# Communication.net
KiCad netlist of a schematic drawn in Altium Designer
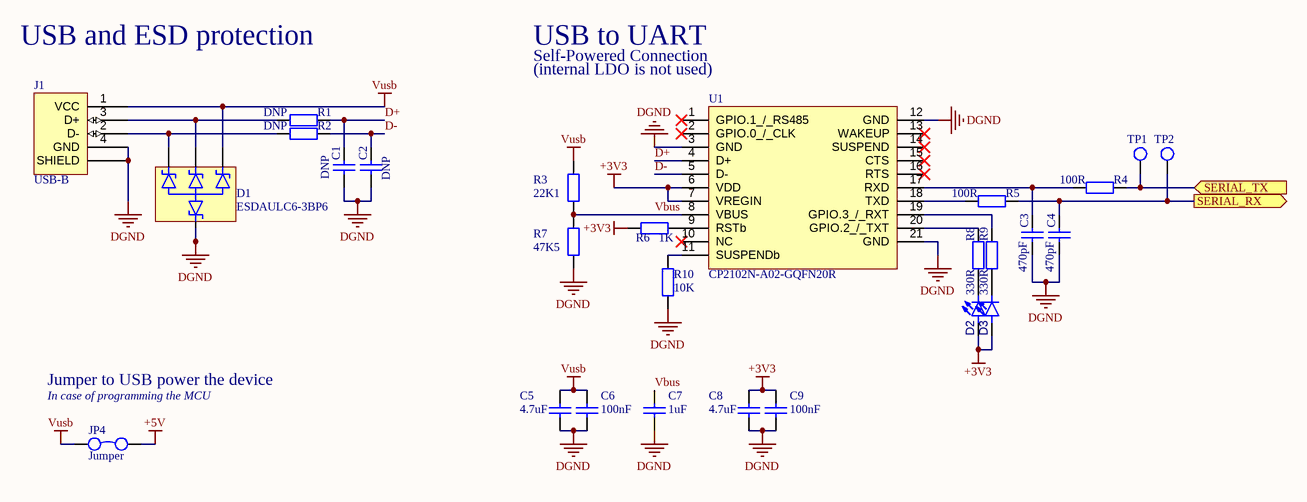
[diagram p0: Communication.SchDoc]

(export (version "E")
  (design (tool "Eeschema 10.0.6"))
  (components
    (comp (ref "C1")
      (value "DNP")
      (footprint "CAP0603")
      (fields
        (field (name "MANUFACTURER") "KEMET")
        (field (name "MANUFACTURER PART NUMBER") "C0603C470J1GACTU")
      )
      (libsource (lib "UPS_Schlib") (part "47pF"))
    )
    (comp (ref "C2")
      (value "DNP")
      (footprint "CAP0603")
      (fields
        (field (name "MANUFACTURER") "KEMET")
        (field (name "MANUFACTURER PART NUMBER") "C0603C470J1GACTU")
      )
      (libsource (lib "UPS_Schlib") (part "47pF"))
    )
    (comp (ref "C3")
      (value "470pF")
      (footprint "CAP0603")
      (fields
        (field (name "MANUFACTURER") "KEMET")
        (field (name "MANUFACTURER PART NUMBER") "C0603C471JAGACAUTO")
      )
      (libsource (lib "UPS_Schlib") (part "470pF"))
    )
    (comp (ref "C4")
      (value "470pF")
      (footprint "CAP0603")
      (fields
        (field (name "MANUFACTURER") "KEMET")
        (field (name "MANUFACTURER PART NUMBER") "C0603C471JAGACAUTO")
      )
      (libsource (lib "UPS_Schlib") (part "470pF"))
    )
    (comp (ref "C5")
      (value "4.7uF")
      (footprint "CAP0603")
      (description "Capacitor Ceramic 4.7uF 10V X5R 10% 0603 T/R")
      (fields
        (field (name "MANUFACTURER") "Samsung")
        (field (name "MANUFACTURER PART NUMBER") "CL10A475KP8NNWC")
      )
      (libsource (lib "UPS_Schlib") (part "4.7uF"))
    )
    (comp (ref "C6")
      (value "100nF")
      (footprint "CAP0603")
      (fields
        (field (name "MANUFACTURER") "Samsung")
        (field (name "MANUFACTURER PART NUMBER") "CL10B104KA8WPNC")
      )
      (libsource (lib "UPS_Schlib") (part "100nF"))
    )
    (comp (ref "C7")
      (value "1uF")
      (footprint "CAP0603")
      (fields
        (field (name "MANUFACTURER") "Walsin Technologies")
        (field (name "MANUFACTURER PART NUMBER") "SH18B105K160CT")
      )
      (libsource (lib "UPS_Schlib") (part "1uF"))
    )
    (comp (ref "C8")
      (value "4.7uF")
      (footprint "CAP0603")
      (description "Capacitor Ceramic 4.7uF 10V X5R 10% 0603 T/R")
      (fields
        (field (name "MANUFACTURER") "Samsung")
        (field (name "MANUFACTURER PART NUMBER") "CL10A475KP8NNWC")
      )
      (libsource (lib "UPS_Schlib") (part "4.7uF"))
    )
    (comp (ref "C9")
      (value "100nF")
      (footprint "CAP0603")
      (fields
        (field (name "MANUFACTURER") "Samsung")
        (field (name "MANUFACTURER PART NUMBER") "CL10B104KA8WPNC")
      )
      (libsource (lib "UPS_Schlib") (part "100nF"))
    )
    (comp (ref "D1")
      (value "ESDAULC6-3BP6")
      (footprint "SOT-666")
      (description "Trans Voltage Suppressor Diode, Bidirectional, 4 Element, Silicon")
      (fields
        (field (name "MOUSER PART NUMBER") "511-ESDAULC63BP6")
        (field (name "MANUFACTURER") "STMicroelectronics")
      )
      (libsource (lib "UPS_Schlib") (part "ESDAULC6-3BP6"))
    )
    (comp (ref "D2")
      (value "~")
      (footprint "LED0603")
      (description "Single Color LED, Bright Green, Water Clear, 1.1mm")
      (fields
        (field (name "MANUFACTURER") "Wurth Electronics")
        (field (name "MANUFACTURER PART NUMBER") "150060VS75000")
      )
      (libsource (lib "UPS_Schlib") (part "LED Green"))
    )
    (comp (ref "D3")
      (value "~")
      (footprint "LED0603")
      (description "Single Color LED, Bright Green, Water Clear, 1.1mm")
      (fields
        (field (name "MANUFACTURER") "Wurth Electronics")
        (field (name "MANUFACTURER PART NUMBER") "150060VS75000")
      )
      (libsource (lib "UPS_Schlib") (part "LED Green"))
    )
    (comp (ref "J1")
      (value "USB-B")
      (footprint "USB-B-FEMALE")
      (description "USB Connector, 4 Contact(s), Female, Right Angle, Solder Terminal, Receptacle")
      (fields
        (field (name "MANUFACTURER") "CUI Devices")
        (field (name "MANUFACTURER PART NUMBER") "UJ2-BH-W2-TH")
      )
      (libsource (lib "UPS_Schlib") (part "USB-B"))
    )
    (comp (ref "JP4")
      (value "Jumper")
      (footprint "PIN-1X2")
      (description "Interconnection Device")
      (fields (field (name "MANUFACTURER") "Harwin") (field (name "MANUFACTURER PART NUMBER") "M7582-46"))
      (libsource (lib "UPS_Schlib") (part "Jumper"))
    )
    (comp (ref "R1")
      (value "DNP")
      (footprint "RES0603")
      (fields
        (field (name "MANUFACTURER") "Vishay")
        (field (name "MANUFACTURER PART NUMBER") "CRCW060320R0FKEA")
      )
      (libsource (lib "UPS_Schlib") (part "20R"))
    )
    (comp (ref "R2")
      (value "DNP")
      (footprint "RES0603")
      (fields
        (field (name "MANUFACTURER") "Vishay")
        (field (name "MANUFACTURER PART NUMBER") "CRCW060320R0FKEA")
      )
      (libsource (lib "UPS_Schlib") (part "20R"))
    )
    (comp (ref "R3")
      (value "22K1")
      (footprint "RES0603")
      (description "22.1K F 1/16 0603")
      (fields
        (field (name "MANUFACTURER") "Mitsubishi Kamaya")
        (field (name "MANUFACTURER PART NUMBER") "RMC1/16K2212FTP")
      )
      (libsource (lib "UPS_Schlib") (part "22K1"))
    )
    (comp (ref "R4")
      (value "100R")
      (footprint "RES0603")
      (fields
        (field (name "MANUFACTURER") "Yageo")
        (field (name "MANUFACTURER PART NUMBER") "RC0603JR-13100RL")
      )
      (libsource (lib "UPS_Schlib") (part "100R"))
    )
    (comp (ref "R5")
      (value "100R")
      (footprint "RES0603")
      (fields
        (field (name "MANUFACTURER") "Yageo")
        (field (name "MANUFACTURER PART NUMBER") "RC0603JR-13100RL")
      )
      (libsource (lib "UPS_Schlib") (part "100R"))
    )
    (comp (ref "R6")
      (value "1K")
      (footprint "RES0603")
      (fields
        (field (name "MANUFACTURER") "Bourns")
        (field (name "MANUFACTURER PART NUMBER") "CR0603-FX-1001ELF")
      )
      (libsource (lib "UPS_Schlib") (part "1K"))
    )
    (comp (ref "R7")
      (value "47K5")
      (footprint "RES0603")
      (fields
        (field (name "MANUFACTURER") "Yageo")
        (field (name "MANUFACTURER PART NUMBER") "RC0603FR-0747K5L")
      )
      (libsource (lib "UPS_Schlib") (part "47K5"))
    )
    (comp (ref "R8")
      (value "330R")
      (footprint "RES0603")
      (fields
        (field (name "MANUFACTURER") "Walsin Technologies")
        (field (name "MANUFACTURER PART NUMBER") "WR06X3300FTL")
      )
      (libsource (lib "UPS_Schlib") (part "330R"))
    )
    (comp (ref "R9")
      (value "330R")
      (footprint "RES0603")
      (fields
        (field (name "MANUFACTURER") "Walsin Technologies")
        (field (name "MANUFACTURER PART NUMBER") "WR06X3300FTL")
      )
      (libsource (lib "UPS_Schlib") (part "330R"))
    )
    (comp (ref "R10")
      (value "10K")
      (footprint "RES0603")
      (fields
        (field (name "MANUFACTURER") "Bourns")
        (field (name "MANUFACTURER PART NUMBER") "CR0603-FX-1002ELF")
      )
      (libsource (lib "UPS_Schlib") (part "10K"))
    )
    (comp (ref "TP1")
      (value "Test Point")
      (footprint "TP-1.5HOLE")
      (libsource (lib "UPS_Schlib") (part "Test Point"))
    )
    (comp (ref "TP2")
      (value "Test Point")
      (footprint "TP-1.5HOLE")
      (libsource (lib "UPS_Schlib") (part "Test Point"))
    )
    (comp (ref "U1")
      (value "CP2102N-A02-GQFN20R")
      (footprint "QFN-20")
      (description "USB Bus Controller, CMOS")
      (fields
        (field (name "MOUSER PART NUMBER") "634-CP2102NA02QFN20R")
        (field (name "MANUFACTURER") "Silicon Labs")
      )
      (libsource (lib "UPS_Schlib") (part "CP2102N-A02-GQFN20R"))
    )
  )
  (nets
    (net (code "1") (name "+3V3") (class "Default")
      (node (ref "C8") (pin "2") (pinfunction "2_2") (pintype "passive"))
      (node (ref "C9") (pin "1") (pinfunction "1_1") (pintype "passive"))
      (node (ref "D2") (pin "2") (pinfunction "A_2") (pintype "passive"))
      (node (ref "D3") (pin "2") (pinfunction "A_2") (pintype "passive"))
      (node (ref "R6") (pin "1") (pinfunction "1_1") (pintype "passive"))
      (node (ref "U1") (pin "6") (pinfunction "VDD_6") (pintype "passive"))
      (node (ref "U1") (pin "7") (pinfunction "VREGIN_7") (pintype "passive"))
    )
    (net (code "2") (name "+5V") (class "Default") (node (ref "JP4") (pin "2") (pintype "passive")))
    (net (code "3") (name "/D+") (class "Default")
      (node (ref "C1") (pin "2") (pinfunction "2_2") (pintype "passive"))
      (node (ref "R1") (pin "1") (pinfunction "1_1") (pintype "passive"))
      (node (ref "U1") (pin "4") (pinfunction "D+_4") (pintype "passive"))
    )
    (net (code "4") (name "/D-") (class "Default")
      (node (ref "C2") (pin "2") (pinfunction "2_2") (pintype "passive"))
      (node (ref "R2") (pin "1") (pinfunction "1_1") (pintype "passive"))
      (node (ref "U1") (pin "5") (pinfunction "D-_5") (pintype "passive"))
    )
    (net (code "5") (name "/SERIAL_RX") (class "Default")
      (node (ref "C4") (pin "2") (pinfunction "2_2") (pintype "passive"))
      (node (ref "R5") (pin "2") (pinfunction "2_2") (pintype "passive"))
      (node (ref "TP2") (pin "1") (pintype "passive"))
    )
    (net (code "6") (name "/SERIAL_TX") (class "Default")
      (node (ref "R4") (pin "2") (pinfunction "2_2") (pintype "passive"))
      (node (ref "TP1") (pin "1") (pintype "passive"))
    )
    (net (code "7") (name "/Vbus") (class "Default")
      (node (ref "C7") (pin "2") (pinfunction "2_2") (pintype "passive"))
      (node (ref "R3") (pin "1") (pinfunction "1_1") (pintype "passive"))
      (node (ref "R7") (pin "2") (pinfunction "2_2") (pintype "passive"))
      (node (ref "U1") (pin "8") (pinfunction "VBUS_8") (pintype "passive"))
    )
    (net (code "8") (name "DGND") (class "Default")
      (node (ref "C1") (pin "1") (pinfunction "1_1") (pintype "passive"))
      (node (ref "C2") (pin "1") (pinfunction "1_1") (pintype "passive"))
      (node (ref "C3") (pin "1") (pinfunction "1_1") (pintype "passive"))
      (node (ref "C4") (pin "1") (pinfunction "1_1") (pintype "passive"))
      (node (ref "C5") (pin "1") (pinfunction "1_1") (pintype "passive"))
      (node (ref "C6") (pin "2") (pinfunction "2_2") (pintype "passive"))
      (node (ref "C7") (pin "1") (pinfunction "1_1") (pintype "passive"))
      (node (ref "C8") (pin "1") (pinfunction "1_1") (pintype "passive"))
      (node (ref "C9") (pin "2") (pinfunction "2_2") (pintype "passive"))
      (node (ref "D1") (pin "6") (pinfunction "GND_6") (pintype "passive"))
      (node (ref "J1") (pin "0") (pinfunction "SHIELD_0") (pintype "passive"))
      (node (ref "J1") (pin "4") (pinfunction "GND_4") (pintype "passive"))
      (node (ref "R10") (pin "1") (pinfunction "1_1") (pintype "passive"))
      (node (ref "R7") (pin "1") (pinfunction "1_1") (pintype "passive"))
      (node (ref "U1") (pin "12") (pinfunction "GND_12") (pintype "passive"))
      (node (ref "U1") (pin "21") (pinfunction "GND_21") (pintype "passive"))
      (node (ref "U1") (pin "3") (pinfunction "GND_3") (pintype "passive"))
    )
    (net (code "9") (name "Net-(D1-I{slash}O1)") (class "Default")
      (node (ref "D1") (pin "1") (pinfunction "I/O1_1") (pintype "passive"))
      (node (ref "J1") (pin "2") (pinfunction "D-_2") (pintype "bidirectional"))
      (node (ref "R2") (pin "2") (pinfunction "2_2") (pintype "passive"))
    )
    (net (code "10") (name "Net-(D1-I{slash}O2)") (class "Default")
      (node (ref "D1") (pin "3") (pinfunction "I/O2_3") (pintype "passive"))
      (node (ref "J1") (pin "3") (pinfunction "D+_3") (pintype "bidirectional"))
      (node (ref "R1") (pin "2") (pinfunction "2_2") (pintype "passive"))
    )
    (net (code "11") (name "Net-(D2-K)") (class "Default")
      (node (ref "D2") (pin "1") (pinfunction "K_1") (pintype "passive"))
      (node (ref "R8") (pin "2") (pinfunction "2_2") (pintype "passive"))
    )
    (net (code "12") (name "Net-(D3-K)") (class "Default")
      (node (ref "D3") (pin "1") (pinfunction "K_1") (pintype "passive"))
      (node (ref "R9") (pin "2") (pinfunction "2_2") (pintype "passive"))
    )
    (net (code "13") (name "Net-(U1-GPIO.2_{slash}_TXT)") (class "Default")
      (node (ref "R8") (pin "1") (pinfunction "1_1") (pintype "passive"))
      (node (ref "U1") (pin "20") (pinfunction "GPIO.2_/_TXT_20") (pintype "passive"))
    )
    (net (code "14") (name "Net-(U1-GPIO.3_{slash}_RXT)") (class "Default")
      (node (ref "R9") (pin "1") (pinfunction "1_1") (pintype "passive"))
      (node (ref "U1") (pin "19") (pinfunction "GPIO.3_/_RXT_19") (pintype "passive"))
    )
    (net (code "15") (name "Net-(U1-RSTb)") (class "Default")
      (node (ref "R6") (pin "2") (pinfunction "2_2") (pintype "passive"))
      (node (ref "U1") (pin "9") (pinfunction "RSTb_9") (pintype "passive"))
    )
    (net (code "16") (name "Net-(U1-RXD)") (class "Default")
      (node (ref "C3") (pin "2") (pinfunction "2_2") (pintype "passive"))
      (node (ref "R4") (pin "1") (pinfunction "1_1") (pintype "passive"))
      (node (ref "U1") (pin "17") (pinfunction "RXD_17") (pintype "passive"))
    )
    (net (code "17") (name "Net-(U1-SUSPENDb)") (class "Default")
      (node (ref "R10") (pin "2") (pinfunction "2_2") (pintype "passive"))
      (node (ref "U1") (pin "11") (pinfunction "SUSPENDb_11") (pintype "passive"))
    )
    (net (code "18") (name "Net-(U1-TXD)") (class "Default")
      (node (ref "R5") (pin "1") (pinfunction "1_1") (pintype "passive"))
      (node (ref "U1") (pin "18") (pinfunction "TXD_18") (pintype "passive"))
    )
    (net (code "19") (name "Vusb") (class "Default")
      (node (ref "C5") (pin "2") (pinfunction "2_2") (pintype "passive"))
      (node (ref "C6") (pin "1") (pinfunction "1_1") (pintype "passive"))
      (node (ref "D1") (pin "4") (pinfunction "I/O3_4") (pintype "passive"))
      (node (ref "J1") (pin "1") (pinfunction "VCC_1") (pintype "power_in"))
      (node (ref "JP4") (pin "1") (pintype "passive"))
      (node (ref "R3") (pin "2") (pinfunction "2_2") (pintype "passive"))
    )
    (net (code "20") (name "unconnected-(U1-CTS-Pad15)") (class "Default")
      (node (ref "U1") (pin "15") (pinfunction "CTS_15") (pintype "passive+no_connect"))
    )
    (net (code "21") (name "unconnected-(U1-GPIO.0_{slash}_CLK-Pad2)") (class "Default")
      (node (ref "U1") (pin "2") (pinfunction "GPIO.0_/_CLK_2") (pintype "passive+no_connect"))
    )
    (net (code "22") (name "unconnected-(U1-GPIO.1_{slash}_RS485-Pad1)") (class "Default")
      (node (ref "U1") (pin "1") (pinfunction "GPIO.1_/_RS485_1") (pintype "passive+no_connect"))
    )
    (net (code "23") (name "unconnected-(U1-NC-Pad10)") (class "Default")
      (node (ref "U1") (pin "10") (pinfunction "NC_10") (pintype "passive+no_connect"))
    )
    (net (code "24") (name "unconnected-(U1-RTS-Pad16)") (class "Default")
      (node (ref "U1") (pin "16") (pinfunction "RTS_16") (pintype "passive+no_connect"))
    )
    (net (code "25") (name "unconnected-(U1-SUSPEND-Pad14)") (class "Default")
      (node (ref "U1") (pin "14") (pinfunction "SUSPEND_14") (pintype "passive+no_connect"))
    )
    (net (code "26") (name "unconnected-(U1-WAKEUP-Pad13)") (class "Default")
      (node (ref "U1") (pin "13") (pinfunction "WAKEUP_13") (pintype "passive+no_connect"))
    )
  )
)
